# blank.net
KiCad netlist of a schematic drawn in EAGLE
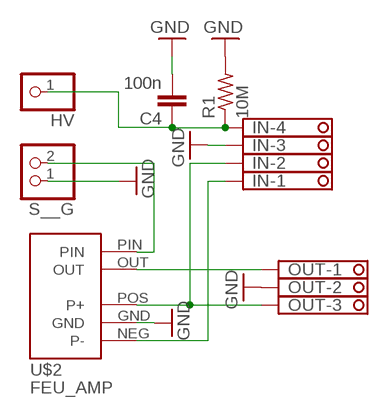
[diagram p0: schematic, sheet 1]

(export (version "E")
  (design (tool "Eeschema 10.0.6"))
  (components
    (comp (ref "C4")
      (value "100n")
      (footprint "eagle-import:C225-087X268")
      (libsource (lib "eagle-import") (part "C-EU225-087X268"))
    )
    (comp (ref "HV")
      (value "PINHD-1X1")
      (footprint "eagle-import:1X01")
      (libsource (lib "eagle-import") (part "PINHD-1X1"))
    )
    (comp (ref "IN")
      (value "1751264")
      (footprint "eagle-import:1751264")
      (libsource (lib "eagle-import") (part "1751264"))
    )
    (comp (ref "OUT")
      (value "1751251")
      (footprint "eagle-import:1751251")
      (libsource (lib "eagle-import") (part "1751251"))
    )
    (comp (ref "R1")
      (value "10M")
      (footprint "eagle-import:0207_2V")
      (libsource (lib "eagle-import") (part "R-US_0207/2V"))
    )
    (comp (ref "S__G")
      (value "PINHD-1X2")
      (footprint "eagle-import:1X02")
      (libsource (lib "eagle-import") (part "PINHD-1X2"))
    )
    (comp (ref "U$2")
      (value "FEU_AMP")
      (footprint "eagle-import:FEU_AMP")
      (libsource (lib "eagle-import") (part "FEU_AMP"))
    )
  )
  (nets
    (net (code "1") (name "GND") (class "Default")
      (node (ref "C4") (pin "2") (pinfunction "2_2") (pintype "passive"))
      (node (ref "IN") (pin "3") (pinfunction "K_3") (pintype "passive"))
      (node (ref "OUT") (pin "2") (pinfunction "K_2") (pintype "passive"))
      (node (ref "R1") (pin "2") (pinfunction "2_2") (pintype "passive"))
      (node (ref "S__G") (pin "1") (pinfunction "1_1") (pintype "passive"))
      (node (ref "U$2") (pin "GND") (pinfunction "GND_GND") (pintype "power_in"))
    )
    (net (code "2") (name "Net-(INA-K)") (class "Default")
      (node (ref "IN") (pin "1") (pinfunction "K_1") (pintype "passive"))
      (node (ref "U$2") (pin "NEG") (pinfunction "P-_NEG") (pintype "power_in"))
    )
    (net (code "3") (name "Net-(INB-K)") (class "Default")
      (node (ref "IN") (pin "2") (pinfunction "K_2") (pintype "passive"))
      (node (ref "OUT") (pin "3") (pinfunction "K_3") (pintype "passive"))
      (node (ref "U$2") (pin "POS") (pinfunction "P+_POS") (pintype "power_in"))
    )
    (net (code "4") (name "Net-(IND-K)") (class "Default")
      (node (ref "C4") (pin "1") (pinfunction "1_1") (pintype "passive"))
      (node (ref "HV") (pin "1") (pinfunction "1_1") (pintype "passive"))
      (node (ref "IN") (pin "4") (pinfunction "K_4") (pintype "passive"))
      (node (ref "R1") (pin "1") (pinfunction "1_1") (pintype "passive"))
    )
    (net (code "5") (name "Net-(OUTA-K)") (class "Default")
      (node (ref "OUT") (pin "1") (pinfunction "K_1") (pintype "passive"))
      (node (ref "U$2") (pin "OUT") (pinfunction "OUT_OUT") (pintype "output"))
    )
    (net (code "6") (name "Net-(S__G-Pad2)") (class "Default")
      (node (ref "S__G") (pin "2") (pinfunction "2_2") (pintype "passive"))
      (node (ref "U$2") (pin "PIN") (pinfunction "PIN_PIN") (pintype "input"))
    )
  )
)
